# schematic.net
KiCad netlist of a schematic drawn in EasyEDA
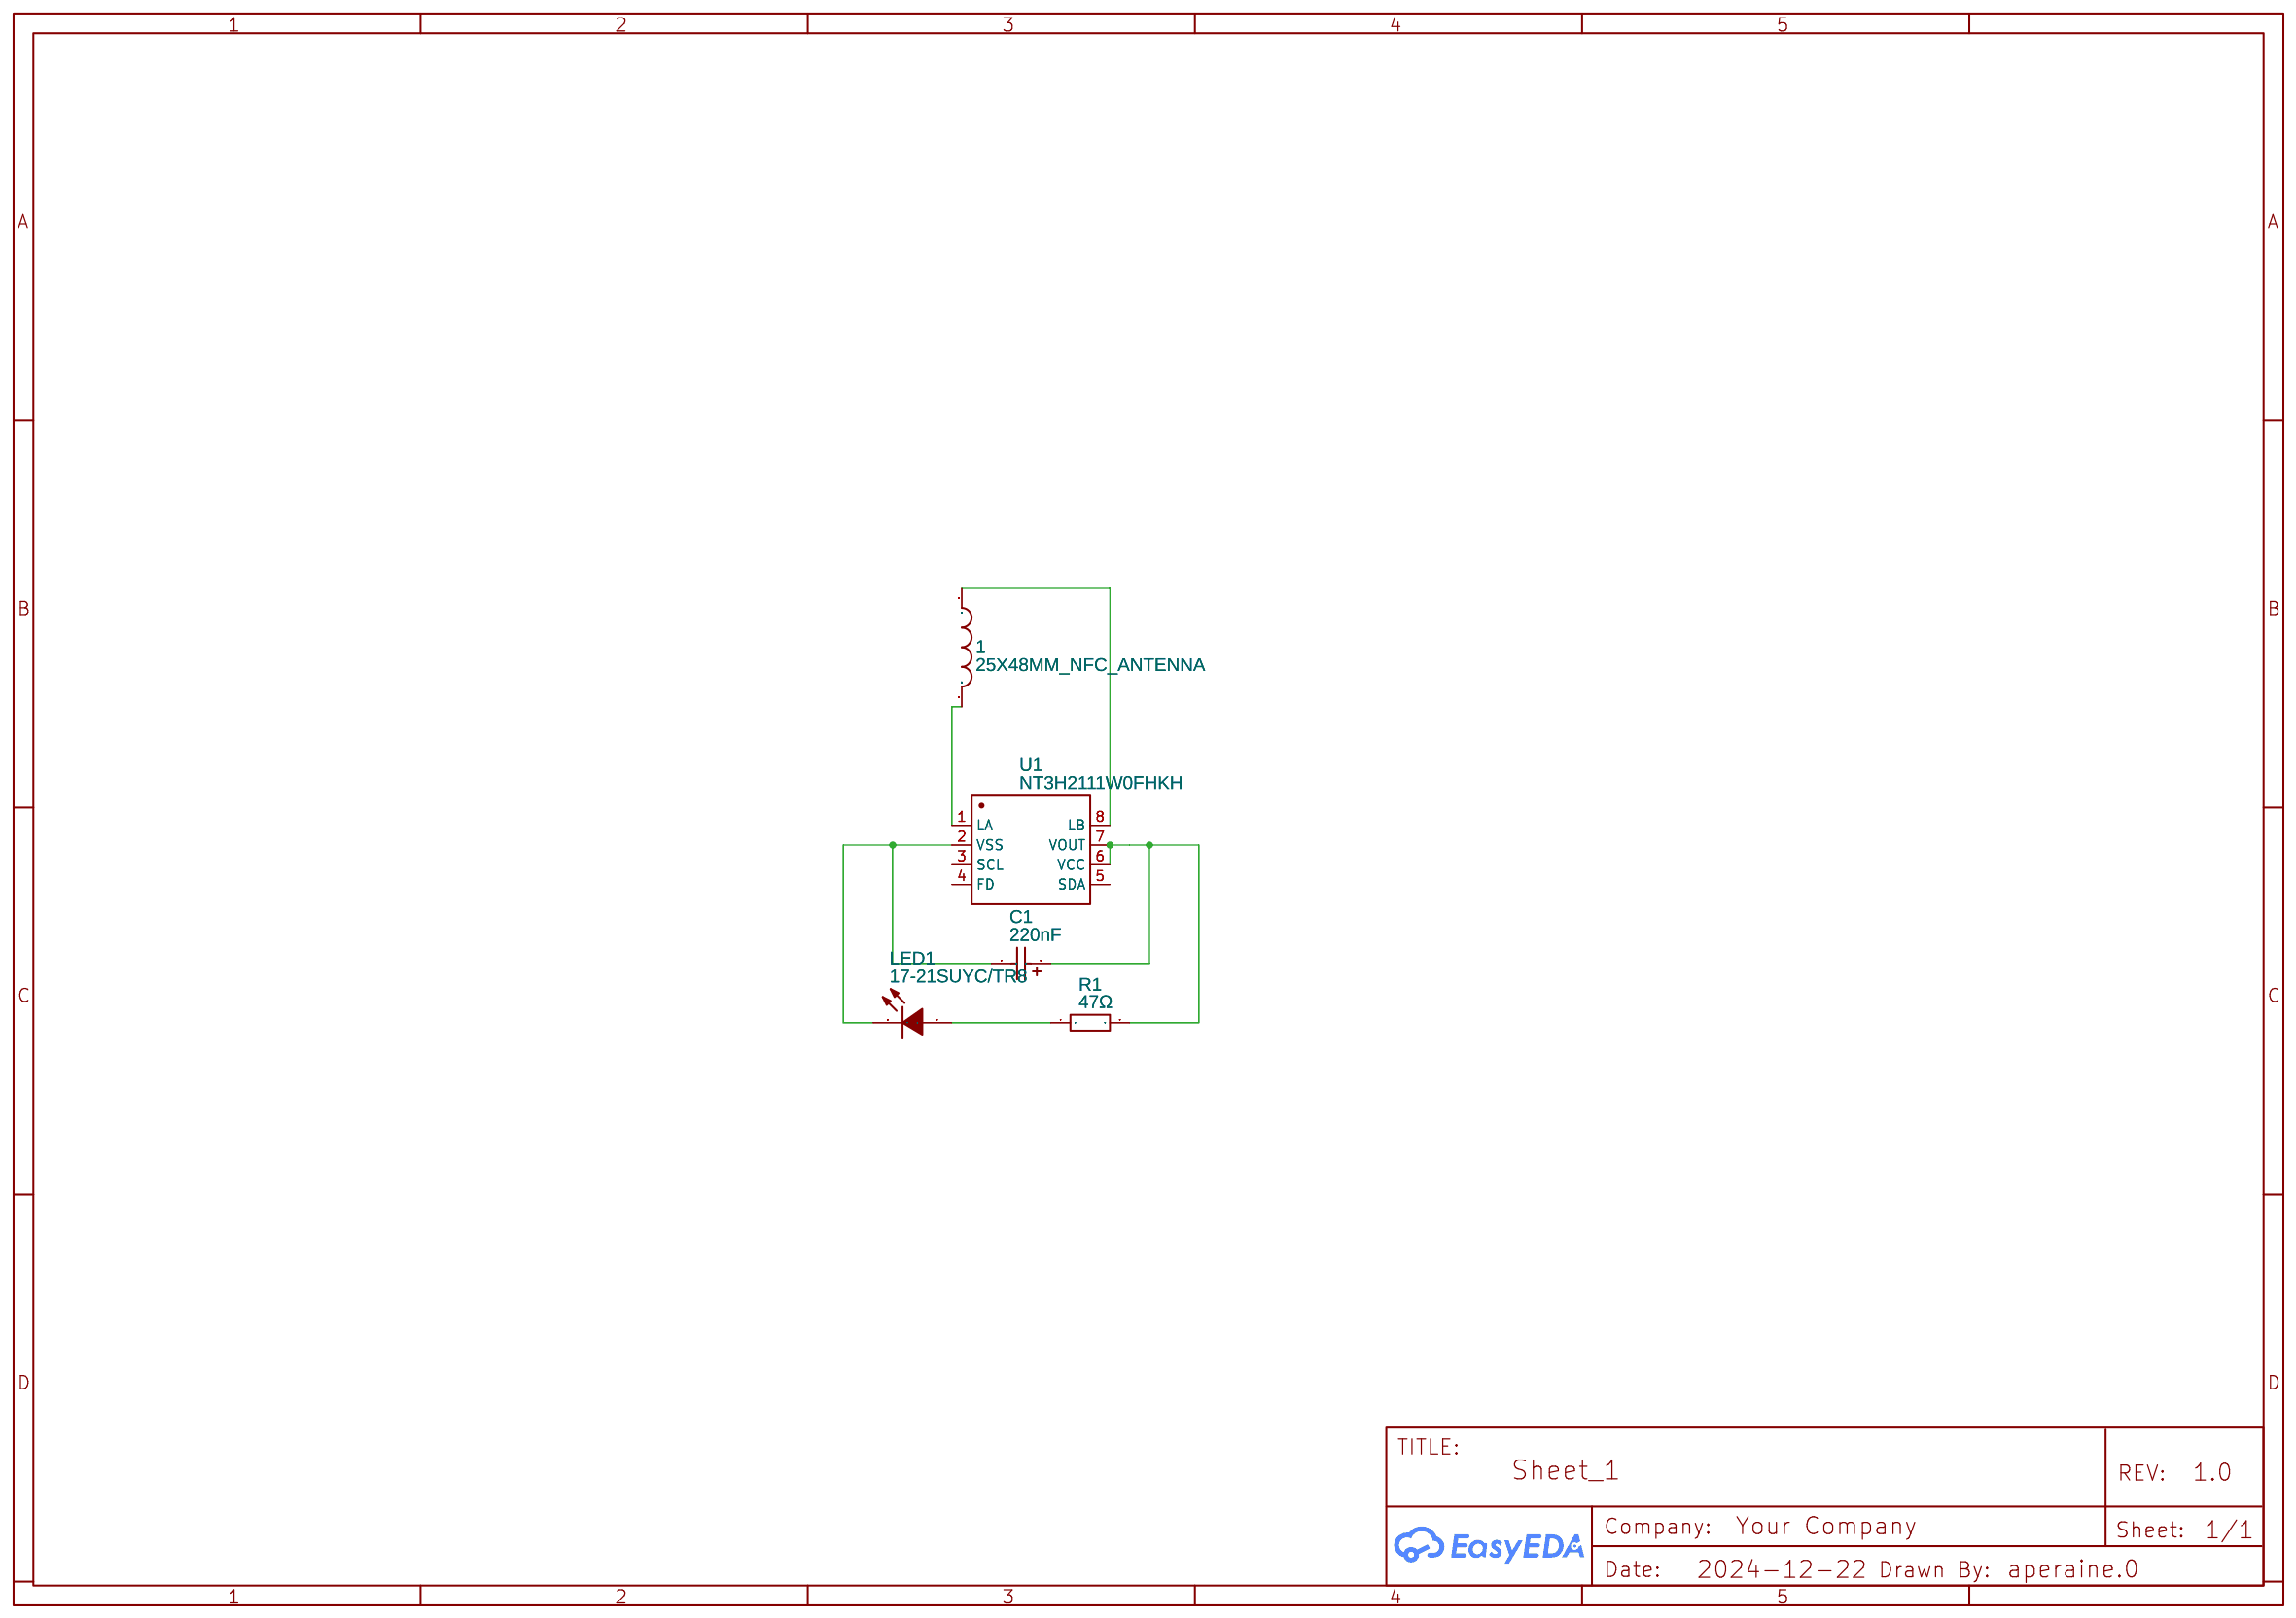
[diagram p0: schematic sheet]

(export (version "E")
  (design (tool "Eeschema 10.0.6"))
  (components
    (comp (ref "1") (value "25X48MM_NFC_ANTENNA") (libsource (lib "") (part "25X48MM_NFC_ANTENNA")))
    (comp (ref "C1")
      (value "220nF")
      (fields (field (name "Manufacturer Part") "TAJA224K035RNJ") (field (name "Manufacturer") "Kyocera AVX"))
      (libsource (lib "") (part "TAJA224K035RNJ"))
    )
    (comp (ref "LED1")
      (value "17-21SUYC/TR8")
      (fields (field (name "Manufacturer Part") "KT-0805黄灯") (field (name "Manufacturer") "KENTO"))
      (libsource (lib "") (part "17-21SUYC/TR8"))
    )
    (comp (ref "R1")
      (value "47Ω")
      (fields
        (field (name "Manufacturer Part") "0603WAJ0470T5E")
        (field (name "Manufacturer") "UNI-ROYAL(厚声)")
      )
      (libsource (lib "") (part "0603WAJ0470T5E"))
    )
    (comp (ref "U1")
      (value "NT3H2111W0FHKH")
      (fields (field (name "Manufacturer") "NXP(恩智浦)"))
      (libsource (lib "") (part "NT3H2111W0FHKH"))
    )
  )
  (nets
    (net (code "1") (name "Net-(LED1-+)") (class "Default")
      (node (ref "LED1") (pin "1") (pinfunction "+_1") (pintype "unspecified"))
      (node (ref "R1") (pin "1") (pinfunction "1_1") (pintype "input"))
    )
    (net (code "2") (name "Net-(LED1--)") (class "Default")
      (node (ref "C1") (pin "2") (pinfunction "2_2") (pintype "input"))
      (node (ref "LED1") (pin "2") (pinfunction "-_2") (pintype "unspecified"))
      (node (ref "U1") (pin "2") (pinfunction "VSS_2") (pintype "unspecified"))
    )
    (net (code "3") (name "Net-(U1-LA)") (class "Default")
      (node (ref "1") (pin "P$2") (pinfunction "P$2_P$2") (pintype "bidirectional"))
      (node (ref "U1") (pin "1") (pinfunction "LA_1") (pintype "unspecified"))
    )
    (net (code "4") (name "Net-(U1-LB)") (class "Default")
      (node (ref "1") (pin "P$1") (pinfunction "P$1_P$1") (pintype "bidirectional"))
      (node (ref "U1") (pin "8") (pinfunction "LB_8") (pintype "unspecified"))
    )
    (net (code "5") (name "Net-(U1-VCC)") (class "Default")
      (node (ref "C1") (pin "1") (pinfunction "1_1") (pintype "input"))
      (node (ref "R1") (pin "2") (pinfunction "2_2") (pintype "input"))
      (node (ref "U1") (pin "6") (pinfunction "VCC_6") (pintype "unspecified"))
      (node (ref "U1") (pin "7") (pinfunction "VOUT_7") (pintype "unspecified"))
    )
    (net (code "6") (name "unconnected-(U1-FD-Pad4)") (class "Default")
      (node (ref "U1") (pin "4") (pinfunction "FD_4") (pintype "unspecified"))
    )
    (net (code "7") (name "unconnected-(U1-SCL-Pad3)") (class "Default")
      (node (ref "U1") (pin "3") (pinfunction "SCL_3") (pintype "unspecified"))
    )
    (net (code "8") (name "unconnected-(U1-SDA-Pad5)") (class "Default")
      (node (ref "U1") (pin "5") (pinfunction "SDA_5") (pintype "unspecified"))
    )
  )
)
